# Pyros.net
KiCad netlist of a schematic drawn in Altium Designer
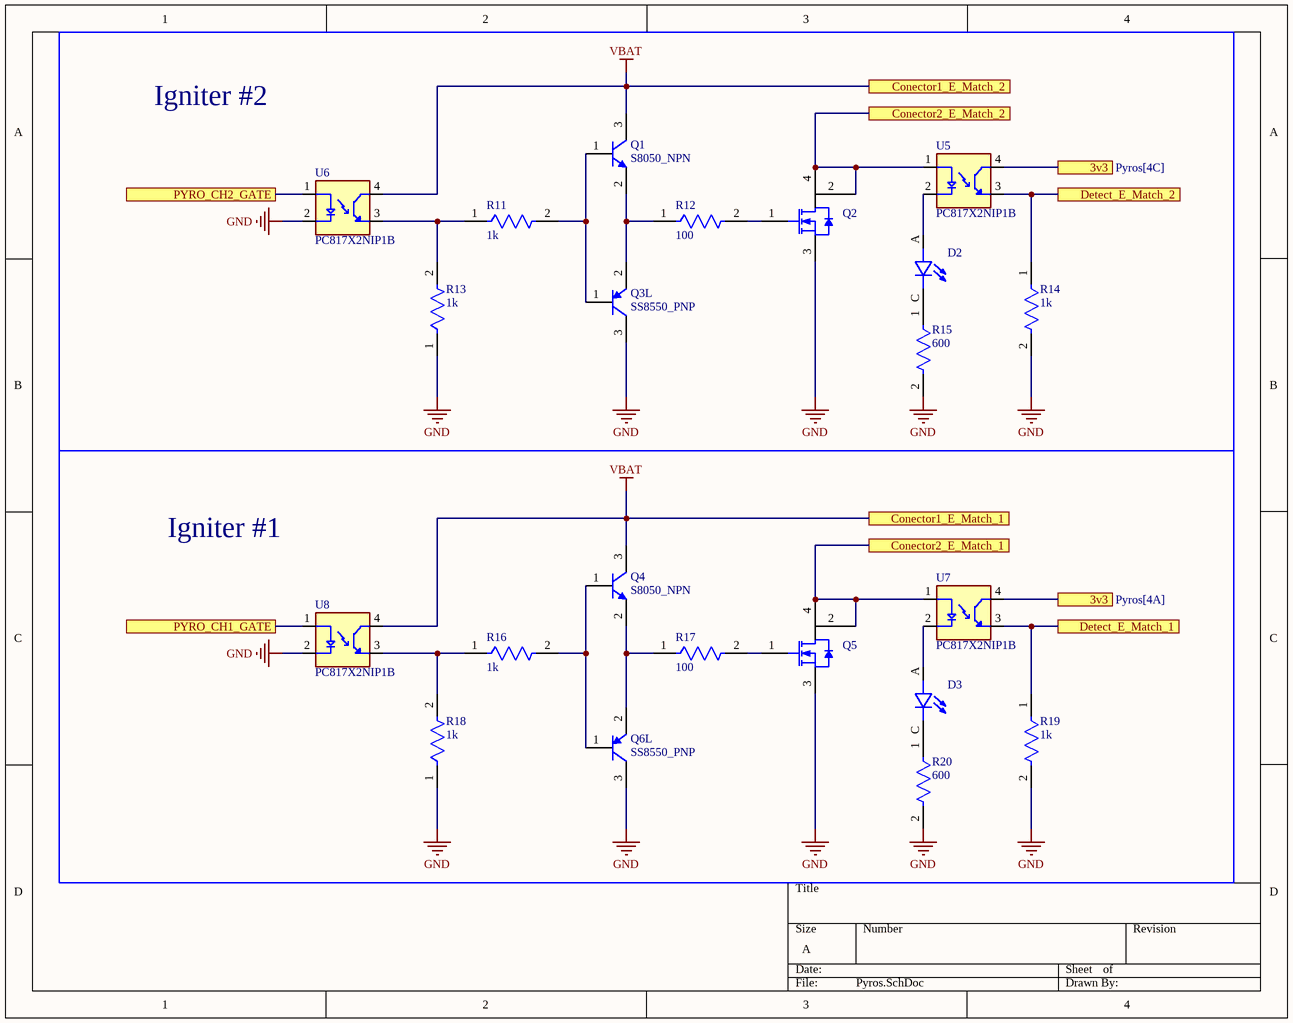
[diagram p0: Pyros.SchDoc]

(export (version "E")
  (design (tool "Eeschema 10.0.6"))
  (components
    (comp (ref "D2")
      (value "SML-LXT0805IW-TR")
      (footprint "LEDC2012X120N")
      (fields (field (name "MF") "Lumex Opto/Components"))
      (libsource (lib "LED_0805-SML-LXT0805IW-TR") (part "SML-LXT0805IW-TR"))
    )
    (comp (ref "D3")
      (value "SML-LXT0805IW-TR")
      (footprint "LEDC2012X120N")
      (fields (field (name "MF") "Lumex Opto/Components"))
      (libsource (lib "LED_0805-SML-LXT0805IW-TR") (part "SML-LXT0805IW-TR"))
    )
    (comp (ref "Q1")
      (value "S8050_NPN")
      (footprint "PCBComponent_1")
      (libsource (lib "NPN_8050") (part "Component_1"))
    )
    (comp (ref "Q2")
      (value "NCE6005AR_Mosfet_N")
      (footprint "PCBComponent_1")
      (libsource (lib "NCE6005AR_Mosfet_N") (part "NCE6005AR"))
    )
    (comp (ref "Q3")
      (value "SS8550_PNP")
      (footprint "PCBComponent_1")
      (libsource (lib "SS8550_PNP") (part "Component_1"))
    )
    (comp (ref "Q4")
      (value "S8050_NPN")
      (footprint "PCBComponent_1")
      (libsource (lib "NPN_8050") (part "Component_1"))
    )
    (comp (ref "Q5")
      (value "NCE6005AR_Mosfet_N")
      (footprint "PCBComponent_1")
      (libsource (lib "NCE6005AR_Mosfet_N") (part "NCE6005AR"))
    )
    (comp (ref "Q6")
      (value "SS8550_PNP")
      (footprint "PCBComponent_1")
      (libsource (lib "SS8550_PNP") (part "Component_1"))
    )
    (comp (ref "R11")
      (value "1k")
      (footprint "FP-MCT0603-IPC_A")
      (description "RES SMD 100 OHM 1% 1/8W 0603")
      (fields (field (name "TOLERANCE") "0.1%"))
      (libsource (lib "Altium Content Vault") (part "1029c3af85768c4190bb7ad29bc67b5"))
    )
    (comp (ref "R12")
      (value "100")
      (footprint "FP-MCT0603-IPC_A")
      (description "RES SMD 100 OHM 1% 1/8W 0603")
      (fields (field (name "TOLERANCE") "0.1%"))
      (libsource (lib "Altium Content Vault") (part "1029c3af85768c4190bb7ad29bc67b5"))
    )
    (comp (ref "R13")
      (value "1k")
      (footprint "FP-MCT0603-IPC_A")
      (description "RES SMD 100 OHM 1% 1/8W 0603")
      (fields (field (name "TOLERANCE") "0.1%"))
      (libsource (lib "Altium Content Vault") (part "1029c3af85768c4190bb7ad29bc67b5"))
    )
    (comp (ref "R14")
      (value "1k")
      (footprint "FP-MCT0603-IPC_A")
      (description "RES SMD 100 OHM 1% 1/8W 0603")
      (fields (field (name "TOLERANCE") "0.1%"))
      (libsource (lib "Altium Content Vault") (part "1029c3af85768c4190bb7ad29bc67b5"))
    )
    (comp (ref "R15")
      (value "600")
      (footprint "FP-MCT0603-IPC_A")
      (description "RES SMD 100 OHM 1% 1/8W 0603")
      (fields (field (name "TOLERANCE") "0.1%"))
      (libsource (lib "Altium Content Vault") (part "1029c3af85768c4190bb7ad29bc67b5"))
    )
    (comp (ref "R16")
      (value "1k")
      (footprint "FP-MCT0603-IPC_A")
      (description "RES SMD 100 OHM 1% 1/8W 0603")
      (fields (field (name "TOLERANCE") "0.1%"))
      (libsource (lib "Altium Content Vault") (part "1029c3af85768c4190bb7ad29bc67b5"))
    )
    (comp (ref "R17")
      (value "100")
      (footprint "FP-MCT0603-IPC_A")
      (description "RES SMD 100 OHM 1% 1/8W 0603")
      (fields (field (name "TOLERANCE") "0.1%"))
      (libsource (lib "Altium Content Vault") (part "1029c3af85768c4190bb7ad29bc67b5"))
    )
    (comp (ref "R18")
      (value "1k")
      (footprint "FP-MCT0603-IPC_A")
      (description "RES SMD 100 OHM 1% 1/8W 0603")
      (fields (field (name "TOLERANCE") "0.1%"))
      (libsource (lib "Altium Content Vault") (part "1029c3af85768c4190bb7ad29bc67b5"))
    )
    (comp (ref "R19")
      (value "1k")
      (footprint "FP-MCT0603-IPC_A")
      (description "RES SMD 100 OHM 1% 1/8W 0603")
      (fields (field (name "TOLERANCE") "0.1%"))
      (libsource (lib "Altium Content Vault") (part "1029c3af85768c4190bb7ad29bc67b5"))
    )
    (comp (ref "R20")
      (value "600")
      (footprint "FP-MCT0603-IPC_A")
      (description "RES SMD 100 OHM 1% 1/8W 0603")
      (fields (field (name "TOLERANCE") "0.1%"))
      (libsource (lib "Altium Content Vault") (part "1029c3af85768c4190bb7ad29bc67b5"))
    )
    (comp (ref "U5")
      (value "PC817X2NIP1B")
      (footprint "SOIC254P960X420-4N")
      (description "Optocoupler DC-IN 1-CH Transistor DC-OUT 4-Pin DIP SMD T/R")
      (fields (field (name "MF") "Sharp Microelectronics"))
      (libsource (lib "Optoisolator-PC817X2NIP1B") (part "PC817X2NIP1B"))
    )
    (comp (ref "U6")
      (value "PC817X2NIP1B")
      (footprint "SOIC254P960X420-4N")
      (description "Optocoupler DC-IN 1-CH Transistor DC-OUT 4-Pin DIP SMD T/R")
      (fields (field (name "MF") "Sharp Microelectronics"))
      (libsource (lib "Optoisolator-PC817X2NIP1B") (part "PC817X2NIP1B"))
    )
    (comp (ref "U7")
      (value "PC817X2NIP1B")
      (footprint "SOIC254P960X420-4N")
      (description "Optocoupler DC-IN 1-CH Transistor DC-OUT 4-Pin DIP SMD T/R")
      (fields (field (name "MF") "Sharp Microelectronics"))
      (libsource (lib "Optoisolator-PC817X2NIP1B") (part "PC817X2NIP1B"))
    )
    (comp (ref "U8")
      (value "PC817X2NIP1B")
      (footprint "SOIC254P960X420-4N")
      (description "Optocoupler DC-IN 1-CH Transistor DC-OUT 4-Pin DIP SMD T/R")
      (fields (field (name "MF") "Sharp Microelectronics"))
      (libsource (lib "Optoisolator-PC817X2NIP1B") (part "PC817X2NIP1B"))
    )
  )
  (nets
    (net (code "1") (name "/3v3") (class "Default")
      (node (ref "U5") (pin "4") (pinfunction "CT_4") (pintype "passive"))
      (node (ref "U7") (pin "4") (pinfunction "CT_4") (pintype "passive"))
    )
    (net (code "2") (name "/Conector2_E_Match_1") (class "Default")
      (node (ref "Q5") (pin "2") (pinfunction "D_2") (pintype "passive"))
      (node (ref "Q5") (pin "4") (pinfunction "D_4") (pintype "passive"))
      (node (ref "U7") (pin "1") (pinfunction "A_1") (pintype "passive"))
    )
    (net (code "3") (name "/Conector2_E_Match_2") (class "Default")
      (node (ref "Q2") (pin "2") (pinfunction "D_2") (pintype "passive"))
      (node (ref "Q2") (pin "4") (pinfunction "D_4") (pintype "passive"))
      (node (ref "U5") (pin "1") (pinfunction "A_1") (pintype "passive"))
    )
    (net (code "4") (name "/Detect_E_Match_1") (class "Default")
      (node (ref "R19") (pin "1") (pinfunction "1_1") (pintype "passive"))
      (node (ref "U7") (pin "3") (pinfunction "ET_3") (pintype "passive"))
    )
    (net (code "5") (name "/Detect_E_Match_2") (class "Default")
      (node (ref "R14") (pin "1") (pinfunction "1_1") (pintype "passive"))
      (node (ref "U5") (pin "3") (pinfunction "ET_3") (pintype "passive"))
    )
    (net (code "6") (name "/PYRO_CH1_GATE") (class "Default")
      (node (ref "U8") (pin "1") (pinfunction "A_1") (pintype "passive"))
    )
    (net (code "7") (name "/PYRO_CH2_GATE") (class "Default")
      (node (ref "U6") (pin "1") (pinfunction "A_1") (pintype "passive"))
    )
    (net (code "8") (name "GND") (class "Default")
      (node (ref "Q2") (pin "3") (pinfunction "S_3") (pintype "passive"))
      (node (ref "Q3") (pin "3") (pinfunction "C_3") (pintype "passive"))
      (node (ref "Q5") (pin "3") (pinfunction "S_3") (pintype "passive"))
      (node (ref "Q6") (pin "3") (pinfunction "C_3") (pintype "passive"))
      (node (ref "R13") (pin "1") (pinfunction "1_1") (pintype "passive"))
      (node (ref "R14") (pin "2") (pinfunction "2_2") (pintype "passive"))
      (node (ref "R15") (pin "2") (pinfunction "2_2") (pintype "passive"))
      (node (ref "R18") (pin "1") (pinfunction "1_1") (pintype "passive"))
      (node (ref "R19") (pin "2") (pinfunction "2_2") (pintype "passive"))
      (node (ref "R20") (pin "2") (pinfunction "2_2") (pintype "passive"))
      (node (ref "U6") (pin "2") (pinfunction "C_2") (pintype "passive"))
      (node (ref "U8") (pin "2") (pinfunction "C_2") (pintype "passive"))
    )
    (net (code "9") (name "Net-(D2-PadC)") (class "Default")
      (node (ref "D2") (pin "C") (pinfunction "C_C") (pintype "passive"))
      (node (ref "R15") (pin "1") (pinfunction "1_1") (pintype "passive"))
    )
    (net (code "10") (name "Net-(D3-PadC)") (class "Default")
      (node (ref "D3") (pin "C") (pinfunction "C_C") (pintype "passive"))
      (node (ref "R20") (pin "1") (pinfunction "1_1") (pintype "passive"))
    )
    (net (code "11") (name "Net-(Q1-B)") (class "Default")
      (node (ref "Q1") (pin "1") (pinfunction "B_1") (pintype "passive"))
      (node (ref "Q3") (pin "1") (pinfunction "B_1") (pintype "passive"))
      (node (ref "R11") (pin "2") (pinfunction "2_2") (pintype "passive"))
    )
    (net (code "12") (name "Net-(Q1-E)") (class "Default")
      (node (ref "Q1") (pin "2") (pinfunction "E_2") (pintype "passive"))
      (node (ref "Q3") (pin "2") (pinfunction "E_2") (pintype "passive"))
      (node (ref "R12") (pin "1") (pinfunction "1_1") (pintype "passive"))
    )
    (net (code "13") (name "Net-(Q2-G)") (class "Default")
      (node (ref "Q2") (pin "1") (pinfunction "G_1") (pintype "passive"))
      (node (ref "R12") (pin "2") (pinfunction "2_2") (pintype "passive"))
    )
    (net (code "14") (name "Net-(Q4-B)") (class "Default")
      (node (ref "Q4") (pin "1") (pinfunction "B_1") (pintype "passive"))
      (node (ref "Q6") (pin "1") (pinfunction "B_1") (pintype "passive"))
      (node (ref "R16") (pin "2") (pinfunction "2_2") (pintype "passive"))
    )
    (net (code "15") (name "Net-(Q4-E)") (class "Default")
      (node (ref "Q4") (pin "2") (pinfunction "E_2") (pintype "passive"))
      (node (ref "Q6") (pin "2") (pinfunction "E_2") (pintype "passive"))
      (node (ref "R17") (pin "1") (pinfunction "1_1") (pintype "passive"))
    )
    (net (code "16") (name "Net-(Q5-G)") (class "Default")
      (node (ref "Q5") (pin "1") (pinfunction "G_1") (pintype "passive"))
      (node (ref "R17") (pin "2") (pinfunction "2_2") (pintype "passive"))
    )
    (net (code "17") (name "Net-(U5-C)") (class "Default")
      (node (ref "D2") (pin "A") (pinfunction "A_A") (pintype "passive"))
      (node (ref "U5") (pin "2") (pinfunction "C_2") (pintype "passive"))
    )
    (net (code "18") (name "Net-(U6-ET)") (class "Default")
      (node (ref "R11") (pin "1") (pinfunction "1_1") (pintype "passive"))
      (node (ref "R13") (pin "2") (pinfunction "2_2") (pintype "passive"))
      (node (ref "U6") (pin "3") (pinfunction "ET_3") (pintype "passive"))
    )
    (net (code "19") (name "Net-(U7-C)") (class "Default")
      (node (ref "D3") (pin "A") (pinfunction "A_A") (pintype "passive"))
      (node (ref "U7") (pin "2") (pinfunction "C_2") (pintype "passive"))
    )
    (net (code "20") (name "Net-(U8-ET)") (class "Default")
      (node (ref "R16") (pin "1") (pinfunction "1_1") (pintype "passive"))
      (node (ref "R18") (pin "2") (pinfunction "2_2") (pintype "passive"))
      (node (ref "U8") (pin "3") (pinfunction "ET_3") (pintype "passive"))
    )
    (net (code "21") (name "VBAT") (class "Default")
      (node (ref "Q1") (pin "3") (pinfunction "C_3") (pintype "passive"))
      (node (ref "Q4") (pin "3") (pinfunction "C_3") (pintype "passive"))
      (node (ref "U6") (pin "4") (pinfunction "CT_4") (pintype "passive"))
      (node (ref "U8") (pin "4") (pinfunction "CT_4") (pintype "passive"))
    )
  )
)
